# schematic.net
KiCad netlist of a schematic drawn in Altium Designer
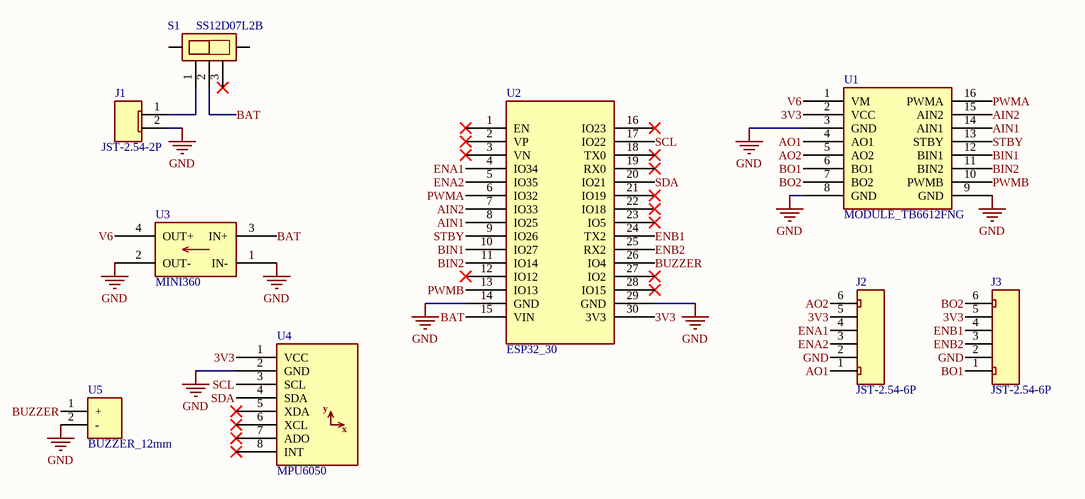
[diagram p0: schematic.SchDoc]

(export (version "E")
  (design (tool "Eeschema 10.0.6"))
  (components
    (comp (ref "J1")
      (value "JST-2.54-2P")
      (footprint "JST-2.54-2P")
      (description "Female Connector JST 2 Vias, 2.54mm.")
      (libsource (lib "Connectors") (part "JST-2.54-2P"))
    )
    (comp (ref "J2")
      (value "JST-2.54-6P")
      (footprint "JST-2.54-6P")
      (description "Female Connector JST 6 Vias, 2.54mm.")
      (libsource (lib "Connectors") (part "JST-2.54-6P"))
    )
    (comp (ref "J3")
      (value "JST-2.54-6P")
      (footprint "JST-2.54-6P")
      (description "Female Connector JST 6 Vias, 2.54mm.")
      (libsource (lib "Connectors") (part "JST-2.54-6P"))
    )
    (comp (ref "S1")
      (value "SS12D07L2B")
      (footprint "SS12D07L2B")
      (description "Vertical Slide Switch 5 Pins 8.7x4.5x4.7mm.")
      (libsource (lib "Buttons & Switches") (part "SS12D07L2B"))
    )
    (comp (ref "U1")
      (value "MODULE_TB6612FNG")
      (footprint "MODULE_TB6612FNG")
      (description "Module Dual Motor Driver 2.5-13.5V 3.2A Peak 21x18mm")
      (libsource (lib "Motor Drivers") (part "MODULE_TB6612FNG"))
    )
    (comp (ref "U2")
      (value "ESP32_30")
      (footprint "ESP32_30")
      (description "Microcontoller Board 30 Pins Wifi 2.4GHz BLE 4.2 ESP32-WROOM-32D")
      (libsource (lib "Espressif Microcontrollers") (part "ESP32_30"))
    )
    (comp (ref "U3")
      (value "MINI360")
      (footprint "MINI360")
      (description "MODULE BUCK STEP DOWN 3A 18x12mm")
      (libsource (lib "Voltage Regulators") (part "MINI360"))
    )
    (comp (ref "U4")
      (value "MPU6050")
      (footprint "MPU6050")
      (description "IMU ACCEL/GYRO 3-AXIS I2C")
      (libsource (lib "Sensors") (part "MPU6050"))
    )
    (comp (ref "U5")
      (value "BUZZER_12mm")
      (footprint "BUZZER_12mm")
      (description "BUZZER MAGNETIC 12MM")
      (libsource (lib "Random") (part "BUZZER_12mm"))
    )
  )
  (nets
    (net (code "1") (name "/3V3") (class "Default")
      (node (ref "J2") (pin "5") (pintype "passive"))
      (node (ref "J3") (pin "5") (pintype "passive"))
      (node (ref "U1") (pin "2") (pinfunction "VCC_2") (pintype "passive"))
      (node (ref "U2") (pin "30") (pinfunction "3V3_30") (pintype "passive"))
      (node (ref "U4") (pin "1") (pinfunction "VCC_1") (pintype "passive"))
    )
    (net (code "2") (name "/AIN1") (class "Default")
      (node (ref "U1") (pin "14") (pinfunction "AIN1_14") (pintype "passive"))
      (node (ref "U2") (pin "8") (pinfunction "IO25_8") (pintype "passive"))
    )
    (net (code "3") (name "/AIN2") (class "Default")
      (node (ref "U1") (pin "15") (pinfunction "AIN2_15") (pintype "passive"))
      (node (ref "U2") (pin "7") (pinfunction "IO33_7") (pintype "passive"))
    )
    (net (code "4") (name "/AO1") (class "Default")
      (node (ref "J2") (pin "1") (pintype "passive"))
      (node (ref "U1") (pin "4") (pinfunction "AO1_4") (pintype "passive"))
    )
    (net (code "5") (name "/AO2") (class "Default")
      (node (ref "J2") (pin "6") (pintype "passive"))
      (node (ref "U1") (pin "5") (pinfunction "AO2_5") (pintype "passive"))
    )
    (net (code "6") (name "/BAT") (class "Default")
      (node (ref "S1") (pin "2") (pinfunction "2_2") (pintype "passive"))
      (node (ref "U2") (pin "15") (pinfunction "VIN_15") (pintype "passive"))
      (node (ref "U3") (pin "3") (pinfunction "IN+_3") (pintype "passive"))
    )
    (net (code "7") (name "/BIN1") (class "Default")
      (node (ref "U1") (pin "12") (pinfunction "BIN1_12") (pintype "passive"))
      (node (ref "U2") (pin "10") (pinfunction "IO27_10") (pintype "passive"))
    )
    (net (code "8") (name "/BIN2") (class "Default")
      (node (ref "U1") (pin "11") (pinfunction "BIN2_11") (pintype "passive"))
      (node (ref "U2") (pin "11") (pinfunction "IO14_11") (pintype "passive"))
    )
    (net (code "9") (name "/BO1") (class "Default")
      (node (ref "J3") (pin "1") (pintype "passive"))
      (node (ref "U1") (pin "6") (pinfunction "BO1_6") (pintype "passive"))
    )
    (net (code "10") (name "/BO2") (class "Default")
      (node (ref "J3") (pin "6") (pintype "passive"))
      (node (ref "U1") (pin "7") (pinfunction "BO2_7") (pintype "passive"))
    )
    (net (code "11") (name "/BUZZER") (class "Default")
      (node (ref "U2") (pin "26") (pinfunction "IO4_26") (pintype "passive"))
      (node (ref "U5") (pin "1") (pinfunction "+_1") (pintype "passive"))
    )
    (net (code "12") (name "/ENA1") (class "Default")
      (node (ref "J2") (pin "4") (pintype "passive"))
      (node (ref "U2") (pin "4") (pinfunction "IO34_4") (pintype "passive"))
    )
    (net (code "13") (name "/ENA2") (class "Default")
      (node (ref "J2") (pin "3") (pintype "passive"))
      (node (ref "U2") (pin "5") (pinfunction "IO35_5") (pintype "passive"))
    )
    (net (code "14") (name "/ENB1") (class "Default")
      (node (ref "J3") (pin "4") (pintype "passive"))
      (node (ref "U2") (pin "24") (pinfunction "TX2_24") (pintype "passive"))
    )
    (net (code "15") (name "/ENB2") (class "Default")
      (node (ref "J3") (pin "3") (pintype "passive"))
      (node (ref "U2") (pin "25") (pinfunction "RX2_25") (pintype "passive"))
    )
    (net (code "16") (name "/PWMA") (class "Default")
      (node (ref "U1") (pin "16") (pinfunction "PWMA_16") (pintype "passive"))
      (node (ref "U2") (pin "6") (pinfunction "IO32_6") (pintype "passive"))
    )
    (net (code "17") (name "/PWMB") (class "Default")
      (node (ref "U1") (pin "10") (pinfunction "PWMB_10") (pintype "passive"))
      (node (ref "U2") (pin "13") (pinfunction "IO13_13") (pintype "passive"))
    )
    (net (code "18") (name "/SCL") (class "Default")
      (node (ref "U2") (pin "17") (pinfunction "IO22_17") (pintype "passive"))
      (node (ref "U4") (pin "3") (pinfunction "SCL_3") (pintype "passive"))
    )
    (net (code "19") (name "/SDA") (class "Default")
      (node (ref "U2") (pin "20") (pinfunction "IO21_20") (pintype "passive"))
      (node (ref "U4") (pin "4") (pinfunction "SDA_4") (pintype "passive"))
    )
    (net (code "20") (name "/STBY") (class "Default")
      (node (ref "U1") (pin "13") (pinfunction "STBY_13") (pintype "passive"))
      (node (ref "U2") (pin "9") (pinfunction "IO26_9") (pintype "passive"))
    )
    (net (code "21") (name "/V6") (class "Default")
      (node (ref "U1") (pin "1") (pinfunction "VM_1") (pintype "passive"))
      (node (ref "U3") (pin "4") (pinfunction "OUT+_4") (pintype "passive"))
    )
    (net (code "22") (name "GND") (class "Default")
      (node (ref "J1") (pin "2") (pintype "passive"))
      (node (ref "J2") (pin "2") (pintype "passive"))
      (node (ref "J3") (pin "2") (pintype "passive"))
      (node (ref "U1") (pin "3") (pinfunction "GND_3") (pintype "passive"))
      (node (ref "U1") (pin "8") (pinfunction "GND_8") (pintype "passive"))
      (node (ref "U1") (pin "9") (pinfunction "GND_9") (pintype "passive"))
      (node (ref "U2") (pin "14") (pinfunction "GND_14") (pintype "passive"))
      (node (ref "U2") (pin "29") (pinfunction "GND_29") (pintype "passive"))
      (node (ref "U3") (pin "1") (pinfunction "IN-_1") (pintype "passive"))
      (node (ref "U3") (pin "2") (pinfunction "OUT-_2") (pintype "passive"))
      (node (ref "U4") (pin "2") (pinfunction "GND_2") (pintype "passive"))
      (node (ref "U5") (pin "2") (pinfunction "-_2") (pintype "passive"))
    )
    (net (code "23") (name "Net-(J1-Pad1)") (class "Default")
      (node (ref "J1") (pin "1") (pintype "passive"))
      (node (ref "S1") (pin "1") (pinfunction "1_1") (pintype "passive"))
    )
    (net (code "24") (name "unconnected-(S1-Pad3)") (class "Default")
      (node (ref "S1") (pin "3") (pinfunction "3_3") (pintype "passive+no_connect"))
    )
    (net (code "25") (name "unconnected-(U2-EN-Pad1)") (class "Default")
      (node (ref "U2") (pin "1") (pinfunction "EN_1") (pintype "passive+no_connect"))
    )
    (net (code "26") (name "unconnected-(U2-IO2-Pad27)") (class "Default")
      (node (ref "U2") (pin "27") (pinfunction "IO2_27") (pintype "passive+no_connect"))
    )
    (net (code "27") (name "unconnected-(U2-IO5-Pad23)") (class "Default")
      (node (ref "U2") (pin "23") (pinfunction "IO5_23") (pintype "passive+no_connect"))
    )
    (net (code "28") (name "unconnected-(U2-IO12-Pad12)") (class "Default")
      (node (ref "U2") (pin "12") (pinfunction "IO12_12") (pintype "passive+no_connect"))
    )
    (net (code "29") (name "unconnected-(U2-IO15-Pad28)") (class "Default")
      (node (ref "U2") (pin "28") (pinfunction "IO15_28") (pintype "passive+no_connect"))
    )
    (net (code "30") (name "unconnected-(U2-IO18-Pad22)") (class "Default")
      (node (ref "U2") (pin "22") (pinfunction "IO18_22") (pintype "passive+no_connect"))
    )
    (net (code "31") (name "unconnected-(U2-IO19-Pad21)") (class "Default")
      (node (ref "U2") (pin "21") (pinfunction "IO19_21") (pintype "passive+no_connect"))
    )
    (net (code "32") (name "unconnected-(U2-IO23-Pad16)") (class "Default")
      (node (ref "U2") (pin "16") (pinfunction "IO23_16") (pintype "passive+no_connect"))
    )
    (net (code "33") (name "unconnected-(U2-RX0-Pad19)") (class "Default")
      (node (ref "U2") (pin "19") (pinfunction "RX0_19") (pintype "passive+no_connect"))
    )
    (net (code "34") (name "unconnected-(U2-TX0-Pad18)") (class "Default")
      (node (ref "U2") (pin "18") (pinfunction "TX0_18") (pintype "passive+no_connect"))
    )
    (net (code "35") (name "unconnected-(U2-VN-Pad3)") (class "Default")
      (node (ref "U2") (pin "3") (pinfunction "VN_3") (pintype "passive+no_connect"))
    )
    (net (code "36") (name "unconnected-(U2-VP-Pad2)") (class "Default")
      (node (ref "U2") (pin "2") (pinfunction "VP_2") (pintype "passive+no_connect"))
    )
    (net (code "37") (name "unconnected-(U4-ADO-Pad7)") (class "Default")
      (node (ref "U4") (pin "7") (pinfunction "ADO_7") (pintype "passive+no_connect"))
    )
    (net (code "38") (name "unconnected-(U4-INT-Pad8)") (class "Default")
      (node (ref "U4") (pin "8") (pinfunction "INT_8") (pintype "passive+no_connect"))
    )
    (net (code "39") (name "unconnected-(U4-XCL-Pad6)") (class "Default")
      (node (ref "U4") (pin "6") (pinfunction "XCL_6") (pintype "passive+no_connect"))
    )
    (net (code "40") (name "unconnected-(U4-XDA-Pad5)") (class "Default")
      (node (ref "U4") (pin "5") (pinfunction "XDA_5") (pintype "passive+no_connect"))
    )
  )
)
